# PhotonIoTv2.net
KiCad netlist of a schematic drawn in EAGLE
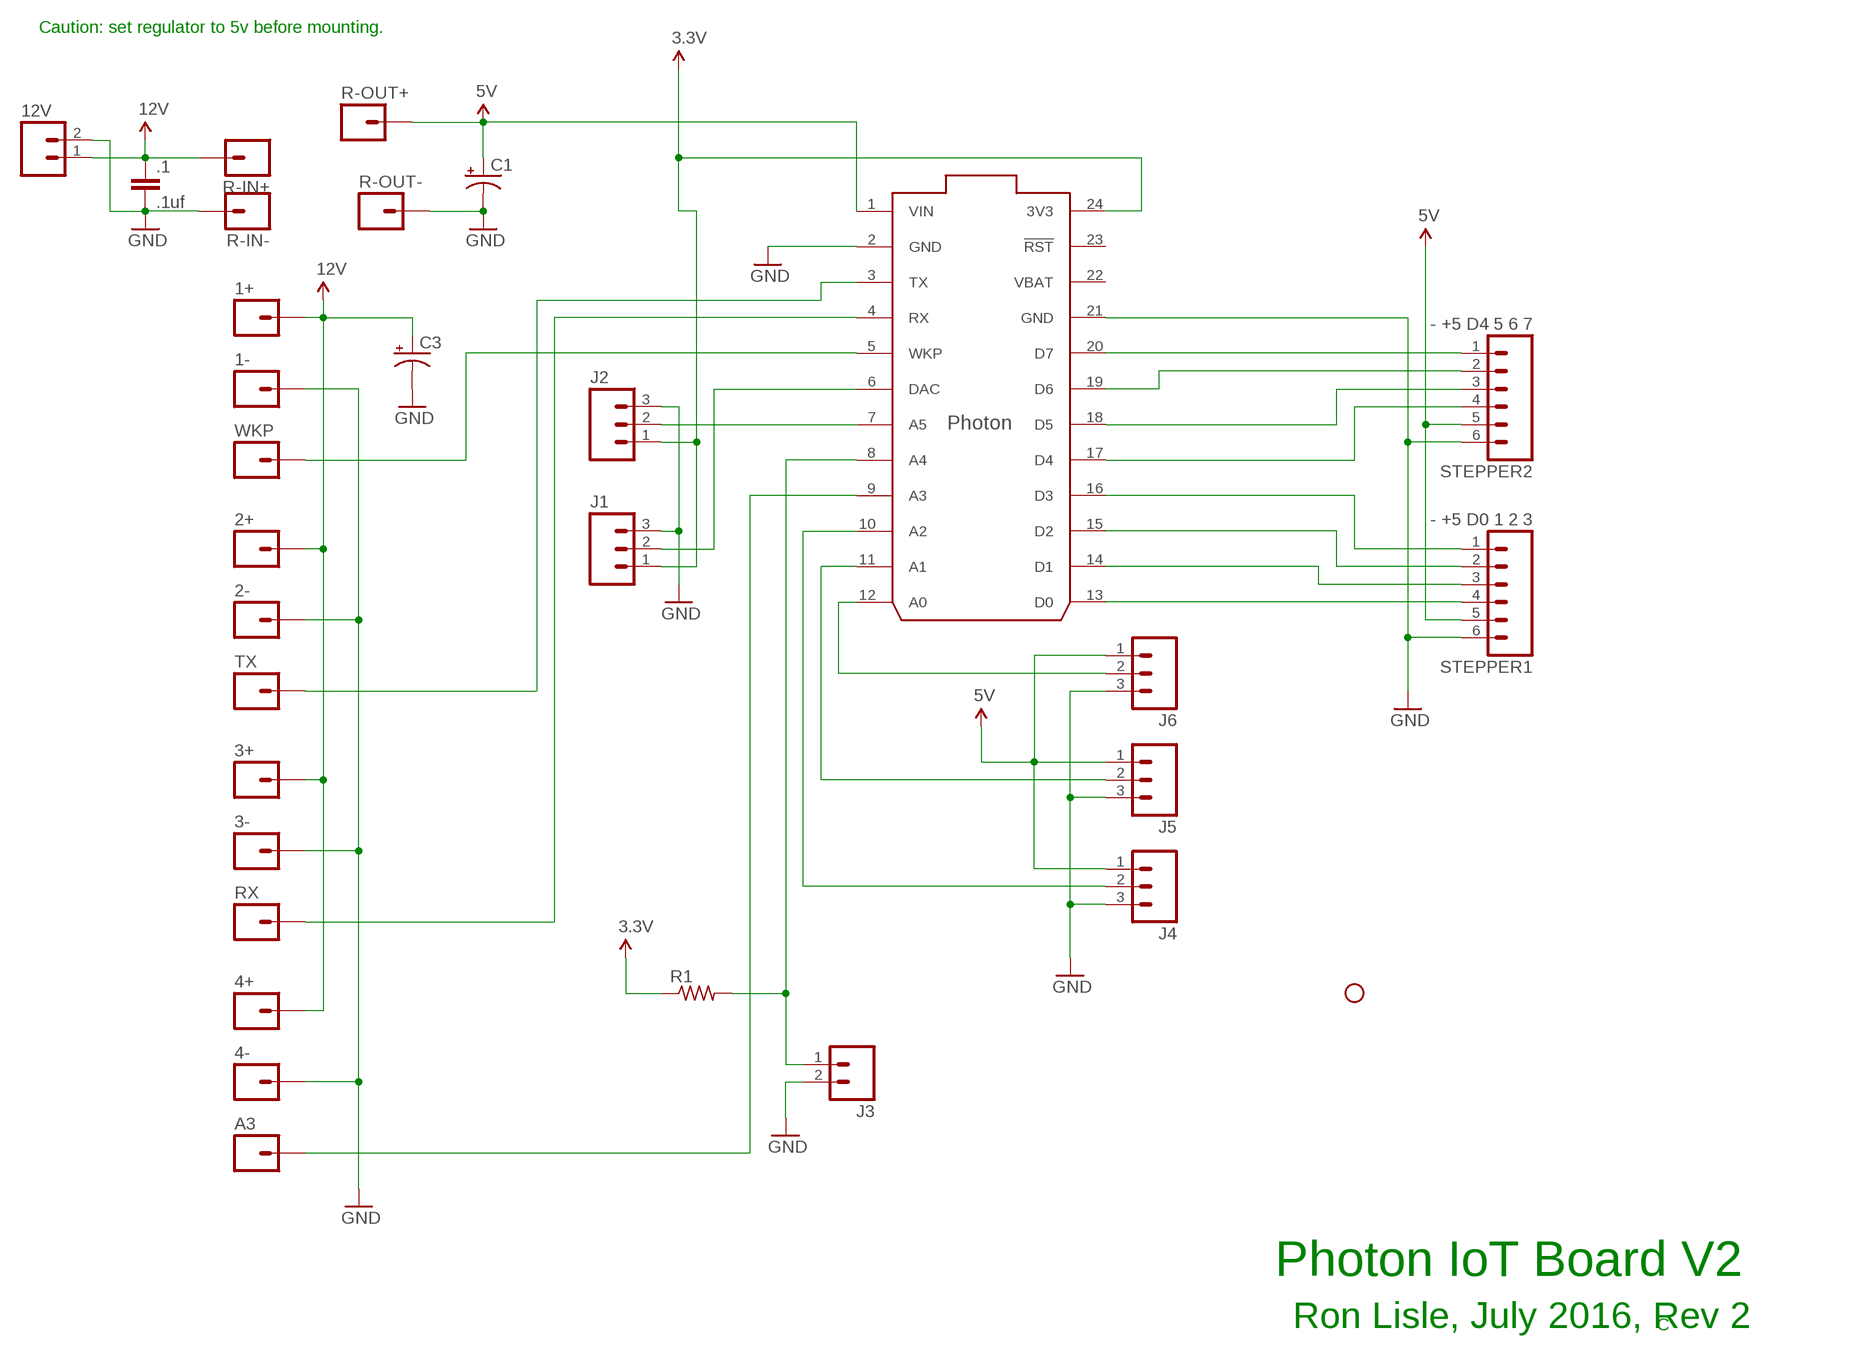
[diagram p0: schematic, sheet 1]

(export (version "E")
  (design (tool "Eeschema 10.0.6"))
  (components
    (comp (ref ".1")
      (value ".1uf")
      (footprint "eagle-import:CAP-PTH-SMALL-KIT")
      (libsource (lib "eagle-import") (part "0.1UF-50V-20%(PTH)KIT-EZ"))
    )
    (comp (ref "1+")
      (value "M01PTH")
      (footprint "eagle-import:1X01")
      (libsource (lib "eagle-import") (part "M01PTH"))
    )
    (comp (ref "1-")
      (value "M01PTH")
      (footprint "eagle-import:1X01")
      (libsource (lib "eagle-import") (part "M01PTH"))
    )
    (comp (ref "2+")
      (value "M01PTH")
      (footprint "eagle-import:1X01")
      (libsource (lib "eagle-import") (part "M01PTH"))
    )
    (comp (ref "2-")
      (value "M01PTH")
      (footprint "eagle-import:1X01")
      (libsource (lib "eagle-import") (part "M01PTH"))
    )
    (comp (ref "3+")
      (value "M01PTH")
      (footprint "eagle-import:1X01")
      (libsource (lib "eagle-import") (part "M01PTH"))
    )
    (comp (ref "3-")
      (value "M01PTH")
      (footprint "eagle-import:1X01")
      (libsource (lib "eagle-import") (part "M01PTH"))
    )
    (comp (ref "4+")
      (value "M01PTH")
      (footprint "eagle-import:1X01")
      (libsource (lib "eagle-import") (part "M01PTH"))
    )
    (comp (ref "4-")
      (value "M01PTH")
      (footprint "eagle-import:1X01")
      (libsource (lib "eagle-import") (part "M01PTH"))
    )
    (comp (ref "12V")
      (value "M025MM")
      (footprint "eagle-import:SCREWTERMINAL-5MM-2")
      (libsource (lib "eagle-import") (part "M025MM"))
    )
    (comp (ref "A3")
      (value "M01PTH")
      (footprint "eagle-import:1X01")
      (libsource (lib "eagle-import") (part "M01PTH"))
    )
    (comp (ref "C1")
      (value "10UF-25V-20%(PTH)KIT")
      (footprint "eagle-import:CPOL-RADIAL-10UF-25V-KIT")
      (libsource (lib "eagle-import") (part "10UF-25V-20%(PTH)KIT"))
    )
    (comp (ref "C3")
      (value "10UF-25V-20%(PTH)KIT")
      (footprint "eagle-import:CPOL-RADIAL-10UF-25V-KIT")
      (libsource (lib "eagle-import") (part "10UF-25V-20%(PTH)KIT"))
    )
    (comp (ref "J1")
      (value "M03PTH")
      (footprint "eagle-import:1X03")
      (libsource (lib "eagle-import") (part "M03PTH"))
    )
    (comp (ref "J2")
      (value "M03PTH")
      (footprint "eagle-import:1X03")
      (libsource (lib "eagle-import") (part "M03PTH"))
    )
    (comp (ref "J3")
      (value "M02PTH")
      (footprint "eagle-import:1X02")
      (libsource (lib "eagle-import") (part "M02PTH"))
    )
    (comp (ref "J4")
      (value "M03PTH")
      (footprint "eagle-import:1X03")
      (libsource (lib "eagle-import") (part "M03PTH"))
    )
    (comp (ref "J5")
      (value "M03PTH")
      (footprint "eagle-import:1X03")
      (libsource (lib "eagle-import") (part "M03PTH"))
    )
    (comp (ref "J6")
      (value "M03PTH")
      (footprint "eagle-import:1X03")
      (libsource (lib "eagle-import") (part "M03PTH"))
    )
    (comp (ref "R-IN+")
      (value "M01PTH")
      (footprint "eagle-import:1X01")
      (libsource (lib "eagle-import") (part "M01PTH"))
    )
    (comp (ref "R-IN-")
      (value "M01PTH")
      (footprint "eagle-import:1X01")
      (libsource (lib "eagle-import") (part "M01PTH"))
    )
    (comp (ref "R-OUT+")
      (value "M01PTH")
      (footprint "eagle-import:1X01")
      (libsource (lib "eagle-import") (part "M01PTH"))
    )
    (comp (ref "R-OUT-")
      (value "M01PTH")
      (footprint "eagle-import:1X01")
      (libsource (lib "eagle-import") (part "M01PTH"))
    )
    (comp (ref "R1")
      (value "R-US_0204/7")
      (footprint "eagle-import:0204_7")
      (libsource (lib "eagle-import") (part "R-US_0204/7"))
    )
    (comp (ref "RX")
      (value "M01PTH")
      (footprint "eagle-import:1X01")
      (libsource (lib "eagle-import") (part "M01PTH"))
    )
    (comp (ref "STANDOFF1")
      (value "STAND-OFF")
      (footprint "eagle-import:STAND-OFF")
      (libsource (lib "eagle-import") (part "STAND-OFF"))
    )
    (comp (ref "STEPPER1")
      (value "- +5 D0 1 2 3")
      (footprint "eagle-import:1X06_LOCK_LONGPADS")
      (libsource (lib "eagle-import") (part "M06LOCK_LONGPADS"))
    )
    (comp (ref "STEPPER2")
      (value "- +5 D4 5 6 7")
      (footprint "eagle-import:1X06_LOCK_LONGPADS")
      (libsource (lib "eagle-import") (part "M06LOCK_LONGPADS"))
    )
    (comp (ref "TX")
      (value "M01PTH")
      (footprint "eagle-import:1X01")
      (libsource (lib "eagle-import") (part "M01PTH"))
    )
    (comp (ref "U$1")
      (value "Photon with headers")
      (footprint "eagle-import:PHOTON")
      (libsource (lib "eagle-import") (part "PHOTON_WITH_HEADERS"))
    )
    (comp (ref "WKP")
      (value "M01PTH")
      (footprint "eagle-import:1X01")
      (libsource (lib "eagle-import") (part "M01PTH"))
    )
  )
  (nets
    (net (code "1") (name "/VBAT") (class "Default")
      (node (ref "U$1") (pin "22") (pinfunction "VBAT_22") (pintype "power_in"))
    )
    (net (code "2") (name "3.3V") (class "Default")
      (node (ref "J1") (pin "1") (pinfunction "1_1") (pintype "passive"))
      (node (ref "J2") (pin "1") (pinfunction "1_1") (pintype "passive"))
      (node (ref "R1") (pin "1") (pinfunction "1_1") (pintype "passive"))
      (node (ref "U$1") (pin "24") (pinfunction "3V3_24") (pintype "power_in"))
    )
    (net (code "3") (name "5V") (class "Default")
      (node (ref "C1") (pin "1") (pinfunction "+_1") (pintype "passive"))
      (node (ref "J4") (pin "1") (pinfunction "1_1") (pintype "passive"))
      (node (ref "J5") (pin "1") (pinfunction "1_1") (pintype "passive"))
      (node (ref "J6") (pin "1") (pinfunction "1_1") (pintype "passive"))
      (node (ref "R-OUT+") (pin "1") (pinfunction "1_1") (pintype "passive"))
      (node (ref "STEPPER1") (pin "5") (pinfunction "5_5") (pintype "passive"))
      (node (ref "STEPPER2") (pin "5") (pinfunction "5_5") (pintype "passive"))
      (node (ref "U$1") (pin "1") (pinfunction "VIN_1") (pintype "power_in"))
    )
    (net (code "4") (name "12V") (class "Default")
      (node (ref ".1") (pin "1") (pinfunction "1_1") (pintype "passive"))
      (node (ref "1+") (pin "1") (pinfunction "1_1") (pintype "passive"))
      (node (ref "12V") (pin "1") (pinfunction "1_1") (pintype "passive"))
      (node (ref "2+") (pin "1") (pinfunction "1_1") (pintype "passive"))
      (node (ref "3+") (pin "1") (pinfunction "1_1") (pintype "passive"))
      (node (ref "4+") (pin "1") (pinfunction "1_1") (pintype "passive"))
      (node (ref "C3") (pin "1") (pinfunction "+_1") (pintype "passive"))
      (node (ref "R-IN+") (pin "1") (pinfunction "1_1") (pintype "passive"))
    )
    (net (code "5") (name "GND") (class "Default")
      (node (ref ".1") (pin "2") (pinfunction "2_2") (pintype "passive"))
      (node (ref "1-") (pin "1") (pinfunction "1_1") (pintype "passive"))
      (node (ref "12V") (pin "2") (pinfunction "2_2") (pintype "passive"))
      (node (ref "2-") (pin "1") (pinfunction "1_1") (pintype "passive"))
      (node (ref "3-") (pin "1") (pinfunction "1_1") (pintype "passive"))
      (node (ref "4-") (pin "1") (pinfunction "1_1") (pintype "passive"))
      (node (ref "C1") (pin "2") (pinfunction "-_2") (pintype "passive"))
      (node (ref "C3") (pin "2") (pinfunction "-_2") (pintype "passive"))
      (node (ref "J1") (pin "3") (pinfunction "3_3") (pintype "passive"))
      (node (ref "J2") (pin "3") (pinfunction "3_3") (pintype "passive"))
      (node (ref "J3") (pin "2") (pinfunction "2_2") (pintype "passive"))
      (node (ref "J4") (pin "3") (pinfunction "3_3") (pintype "passive"))
      (node (ref "J5") (pin "3") (pinfunction "3_3") (pintype "passive"))
      (node (ref "J6") (pin "3") (pinfunction "3_3") (pintype "passive"))
      (node (ref "R-IN-") (pin "1") (pinfunction "1_1") (pintype "passive"))
      (node (ref "R-OUT-") (pin "1") (pinfunction "1_1") (pintype "passive"))
      (node (ref "STEPPER1") (pin "6") (pinfunction "6_6") (pintype "passive"))
      (node (ref "STEPPER2") (pin "6") (pinfunction "6_6") (pintype "passive"))
      (node (ref "U$1") (pin "2") (pinfunction "GND_2") (pintype "power_in"))
      (node (ref "U$1") (pin "21") (pinfunction "GND_21") (pintype "power_in"))
    )
    (net (code "6") (name "Net-(U$1-A0)") (class "Default")
      (node (ref "J6") (pin "2") (pinfunction "2_2") (pintype "passive"))
      (node (ref "U$1") (pin "12") (pinfunction "A0_12") (pintype "bidirectional"))
    )
    (net (code "7") (name "Net-(U$1-A1)") (class "Default")
      (node (ref "J5") (pin "2") (pinfunction "2_2") (pintype "passive"))
      (node (ref "U$1") (pin "11") (pinfunction "A1_11") (pintype "bidirectional"))
    )
    (net (code "8") (name "Net-(U$1-A2)") (class "Default")
      (node (ref "J4") (pin "2") (pinfunction "2_2") (pintype "passive"))
      (node (ref "U$1") (pin "10") (pinfunction "A2_10") (pintype "bidirectional"))
    )
    (net (code "9") (name "Net-(U$1-A3)") (class "Default")
      (node (ref "A3") (pin "1") (pinfunction "1_1") (pintype "passive"))
      (node (ref "U$1") (pin "9") (pinfunction "A3_9") (pintype "bidirectional"))
    )
    (net (code "10") (name "Net-(U$1-A4)") (class "Default")
      (node (ref "J3") (pin "1") (pinfunction "1_1") (pintype "passive"))
      (node (ref "R1") (pin "2") (pinfunction "2_2") (pintype "passive"))
      (node (ref "U$1") (pin "8") (pinfunction "A4_8") (pintype "bidirectional"))
    )
    (net (code "11") (name "Net-(U$1-A5)") (class "Default")
      (node (ref "J2") (pin "2") (pinfunction "2_2") (pintype "passive"))
      (node (ref "U$1") (pin "7") (pinfunction "A5_7") (pintype "bidirectional"))
    )
    (net (code "12") (name "Net-(U$1-D0)") (class "Default")
      (node (ref "STEPPER1") (pin "4") (pinfunction "4_4") (pintype "passive"))
      (node (ref "U$1") (pin "13") (pinfunction "D0_13") (pintype "bidirectional"))
    )
    (net (code "13") (name "Net-(U$1-D1)") (class "Default")
      (node (ref "STEPPER1") (pin "3") (pinfunction "3_3") (pintype "passive"))
      (node (ref "U$1") (pin "14") (pinfunction "D1_14") (pintype "bidirectional"))
    )
    (net (code "14") (name "Net-(U$1-D2)") (class "Default")
      (node (ref "STEPPER1") (pin "2") (pinfunction "2_2") (pintype "passive"))
      (node (ref "U$1") (pin "15") (pinfunction "D2_15") (pintype "bidirectional"))
    )
    (net (code "15") (name "Net-(U$1-D3)") (class "Default")
      (node (ref "STEPPER1") (pin "1") (pinfunction "1_1") (pintype "passive"))
      (node (ref "U$1") (pin "16") (pinfunction "D3_16") (pintype "bidirectional"))
    )
    (net (code "16") (name "Net-(U$1-D4)") (class "Default")
      (node (ref "STEPPER2") (pin "4") (pinfunction "4_4") (pintype "passive"))
      (node (ref "U$1") (pin "17") (pinfunction "D4_17") (pintype "bidirectional"))
    )
    (net (code "17") (name "Net-(U$1-D5)") (class "Default")
      (node (ref "STEPPER2") (pin "3") (pinfunction "3_3") (pintype "passive"))
      (node (ref "U$1") (pin "18") (pinfunction "D5_18") (pintype "bidirectional"))
    )
    (net (code "18") (name "Net-(U$1-D6)") (class "Default")
      (node (ref "STEPPER2") (pin "2") (pinfunction "2_2") (pintype "passive"))
      (node (ref "U$1") (pin "19") (pinfunction "D6_19") (pintype "bidirectional"))
    )
    (net (code "19") (name "Net-(U$1-D7)") (class "Default")
      (node (ref "STEPPER2") (pin "1") (pinfunction "1_1") (pintype "passive"))
      (node (ref "U$1") (pin "20") (pinfunction "D7_20") (pintype "bidirectional"))
    )
    (net (code "20") (name "Net-(U$1-DAC)") (class "Default")
      (node (ref "J1") (pin "2") (pinfunction "2_2") (pintype "passive"))
      (node (ref "U$1") (pin "6") (pinfunction "DAC_6") (pintype "bidirectional"))
    )
    (net (code "21") (name "Net-(U$1-RX)") (class "Default")
      (node (ref "RX") (pin "1") (pinfunction "1_1") (pintype "passive"))
      (node (ref "U$1") (pin "4") (pinfunction "RX_4") (pintype "bidirectional"))
    )
    (net (code "22") (name "Net-(U$1-TX)") (class "Default")
      (node (ref "TX") (pin "1") (pinfunction "1_1") (pintype "passive"))
      (node (ref "U$1") (pin "3") (pinfunction "TX_3") (pintype "bidirectional"))
    )
    (net (code "23") (name "Net-(U$1-WKP)") (class "Default")
      (node (ref "U$1") (pin "5") (pinfunction "WKP_5") (pintype "bidirectional"))
      (node (ref "WKP") (pin "1") (pinfunction "1_1") (pintype "passive"))
    )
    (net (code "24") (name "unconnected-(U$1-~{RST}-Pad23)") (class "Default")
      (node (ref "U$1") (pin "23") (pinfunction "~{RST}_23") (pintype "bidirectional"))
    )
  )
)
